# Buck_Modules.net
KiCad netlist of a schematic drawn in Altium Designer
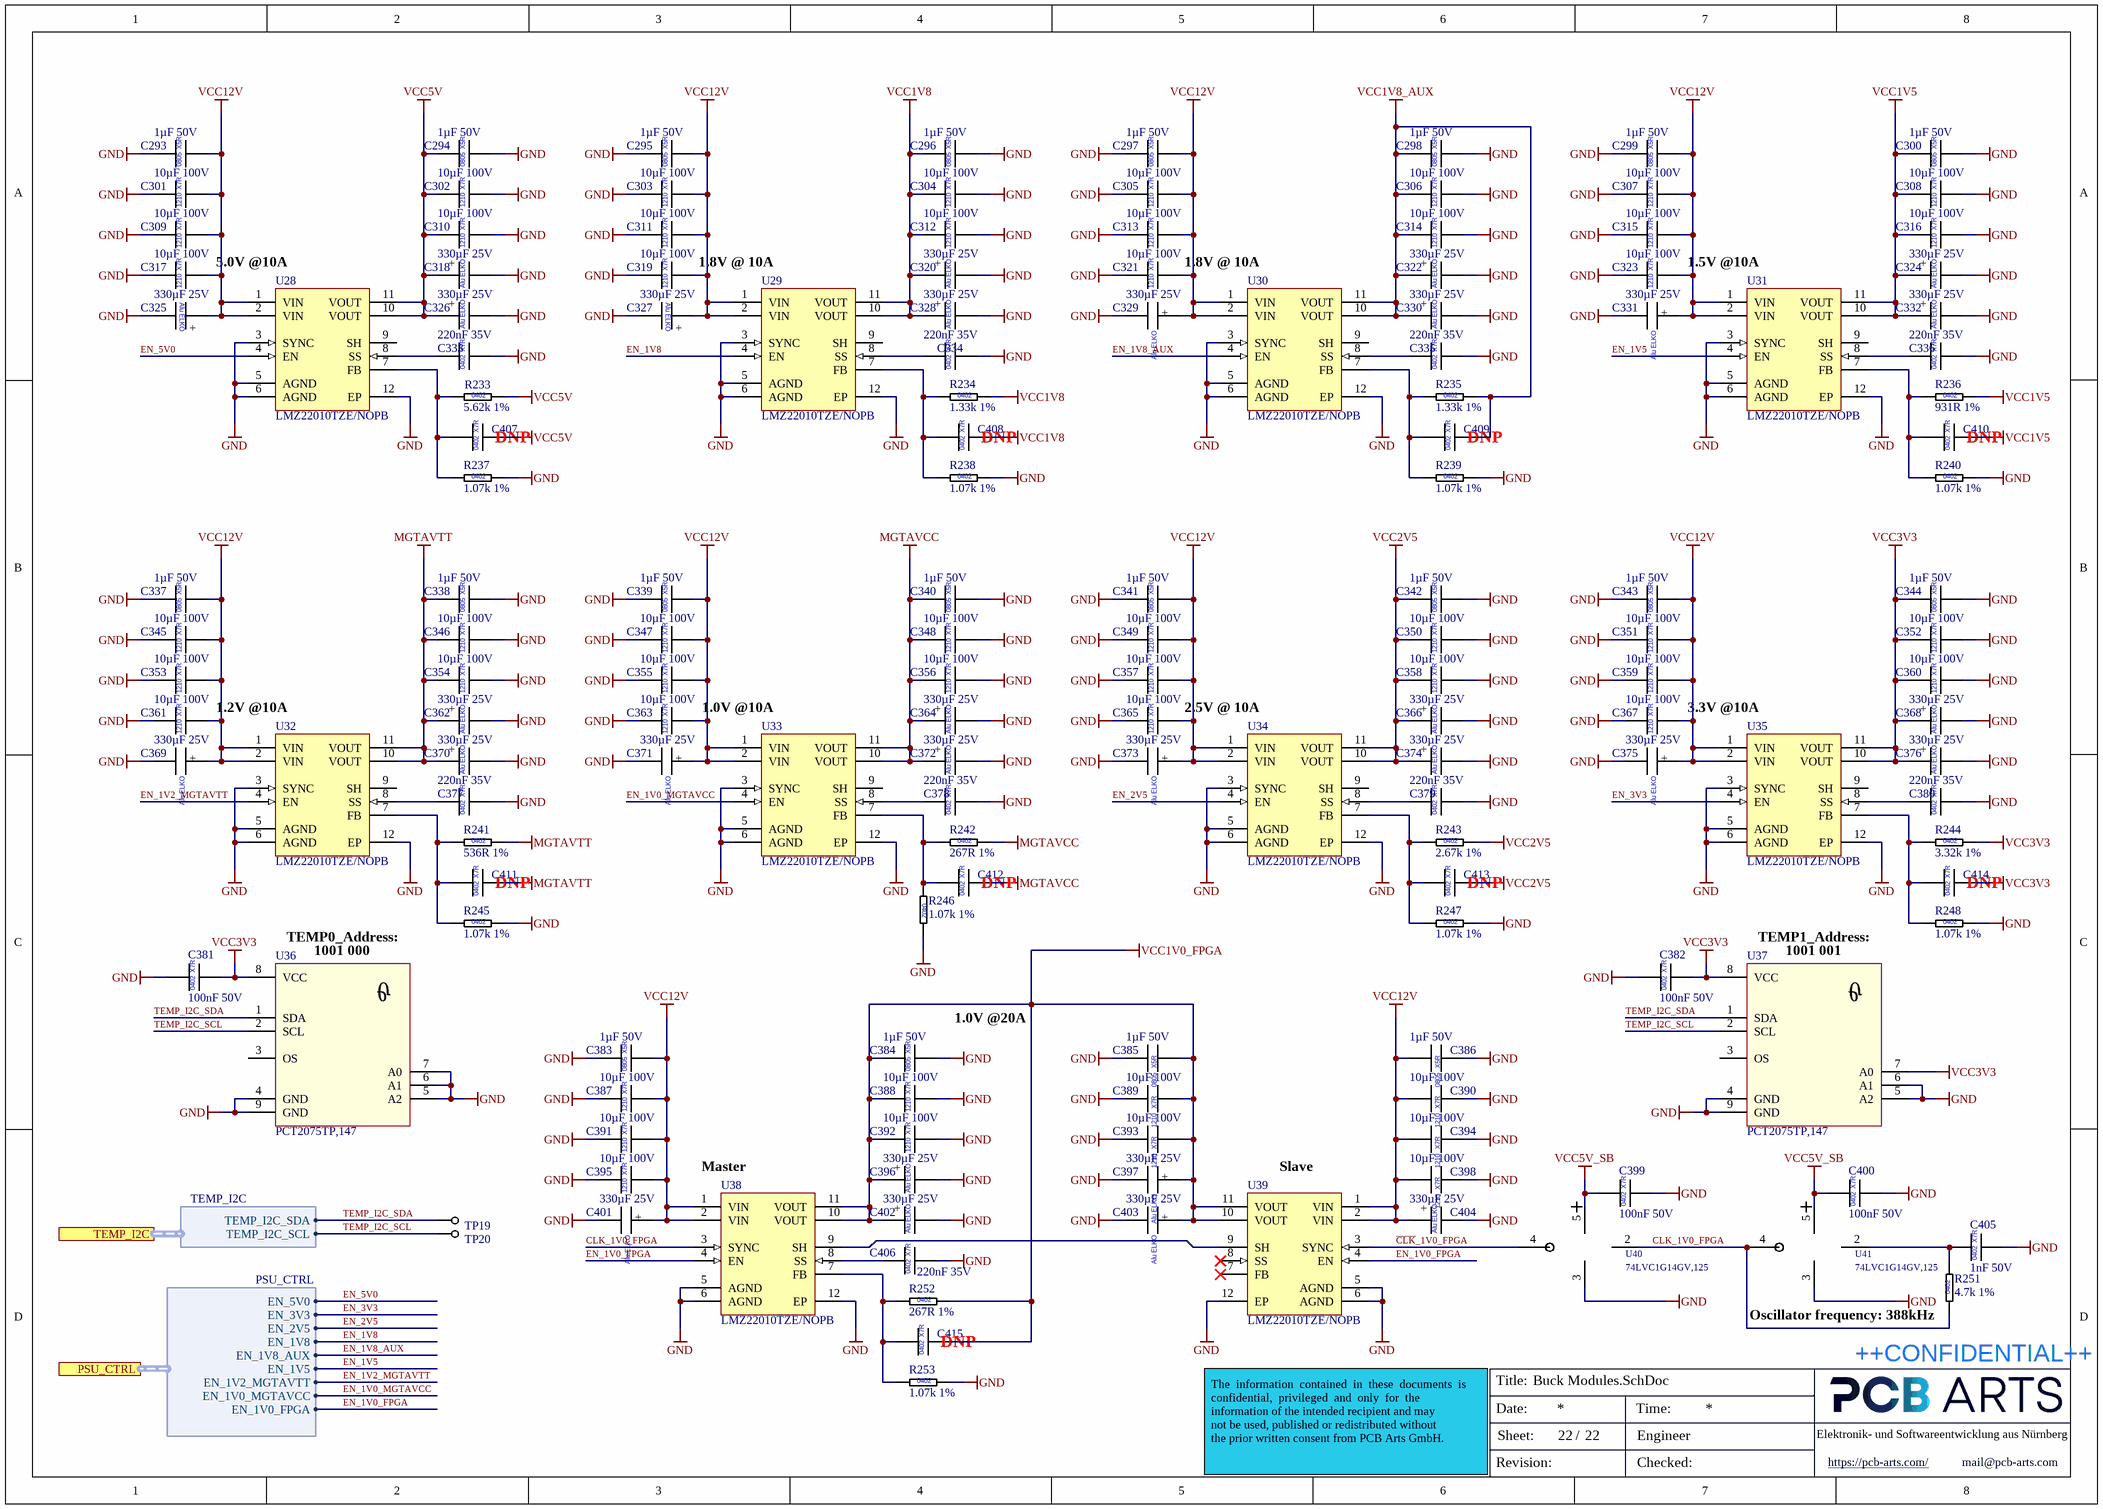
[diagram p0: Buck Modules.SchDoc]

(export (version "E")
  (design (tool "Eeschema 10.0.6"))
  (components
    (comp (ref "C293")
      (value "1µF 50V")
      (footprint "Cap:CAP_0805")
      (description "Multilayer Ceramic Capacitors MLCC - SMD/SMT 0805 50VDC")
      (libsource (lib "Cap") (part "CAP_0805_1µF_50V"))
    )
    (comp (ref "C294")
      (value "1µF 50V")
      (footprint "Cap:CAP_0805")
      (description "Multilayer Ceramic Capacitors MLCC - SMD/SMT 0805 50VDC")
      (libsource (lib "Cap") (part "CAP_0805_1µF_50V"))
    )
    (comp (ref "C295")
      (value "1µF 50V")
      (footprint "Cap:CAP_0805")
      (description "Multilayer Ceramic Capacitors MLCC - SMD/SMT 0805 50VDC")
      (libsource (lib "Cap") (part "CAP_0805_1µF_50V"))
    )
    (comp (ref "C296")
      (value "1µF 50V")
      (footprint "Cap:CAP_0805")
      (description "Multilayer Ceramic Capacitors MLCC - SMD/SMT 0805 50VDC")
      (libsource (lib "Cap") (part "CAP_0805_1µF_50V"))
    )
    (comp (ref "C297")
      (value "1µF 50V")
      (footprint "Cap:CAP_0805")
      (description "Multilayer Ceramic Capacitors MLCC - SMD/SMT 0805 50VDC")
      (libsource (lib "Cap") (part "CAP_0805_1µF_50V"))
    )
    (comp (ref "C298")
      (value "1µF 50V")
      (footprint "Cap:CAP_0805")
      (description "Multilayer Ceramic Capacitors MLCC - SMD/SMT 0805 50VDC")
      (libsource (lib "Cap") (part "CAP_0805_1µF_50V"))
    )
    (comp (ref "C299")
      (value "1µF 50V")
      (footprint "Cap:CAP_0805")
      (description "Multilayer Ceramic Capacitors MLCC - SMD/SMT 0805 50VDC")
      (libsource (lib "Cap") (part "CAP_0805_1µF_50V"))
    )
    (comp (ref "C300")
      (value "1µF 50V")
      (footprint "Cap:CAP_0805")
      (description "Multilayer Ceramic Capacitors MLCC - SMD/SMT 0805 50VDC")
      (libsource (lib "Cap") (part "CAP_0805_1µF_50V"))
    )
    (comp (ref "C301")
      (value "10µF 100V")
      (footprint "Cap:CAP_1210")
      (description "Multilayer Ceramic Capacitors MLCC - SMD/SMT 1210 100VDC")
      (libsource (lib "") (part "CAP_1210_10µF_100V_1"))
    )
    (comp (ref "C302")
      (value "10µF 100V")
      (footprint "Cap:CAP_1210")
      (description "Multilayer Ceramic Capacitors MLCC - SMD/SMT 1210 100VDC")
      (libsource (lib "") (part "CAP_1210_10µF_100V_1"))
    )
    (comp (ref "C303")
      (value "10µF 100V")
      (footprint "Cap:CAP_1210")
      (description "Multilayer Ceramic Capacitors MLCC - SMD/SMT 1210 100VDC")
      (libsource (lib "") (part "CAP_1210_10µF_100V_1"))
    )
    (comp (ref "C304")
      (value "10µF 100V")
      (footprint "Cap:CAP_1210")
      (description "Multilayer Ceramic Capacitors MLCC - SMD/SMT 1210 100VDC")
      (libsource (lib "") (part "CAP_1210_10µF_100V_1"))
    )
    (comp (ref "C305")
      (value "10µF 100V")
      (footprint "Cap:CAP_1210")
      (description "Multilayer Ceramic Capacitors MLCC - SMD/SMT 1210 100VDC")
      (libsource (lib "") (part "CAP_1210_10µF_100V_1"))
    )
    (comp (ref "C306")
      (value "10µF 100V")
      (footprint "Cap:CAP_1210")
      (description "Multilayer Ceramic Capacitors MLCC - SMD/SMT 1210 100VDC")
      (libsource (lib "") (part "CAP_1210_10µF_100V_1"))
    )
    (comp (ref "C307")
      (value "10µF 100V")
      (footprint "Cap:CAP_1210")
      (description "Multilayer Ceramic Capacitors MLCC - SMD/SMT 1210 100VDC")
      (libsource (lib "") (part "CAP_1210_10µF_100V_1"))
    )
    (comp (ref "C308")
      (value "10µF 100V")
      (footprint "Cap:CAP_1210")
      (description "Multilayer Ceramic Capacitors MLCC - SMD/SMT 1210 100VDC")
      (libsource (lib "") (part "CAP_1210_10µF_100V_1"))
    )
    (comp (ref "C309")
      (value "10µF 100V")
      (footprint "Cap:CAP_1210")
      (description "Multilayer Ceramic Capacitors MLCC - SMD/SMT 1210 100VDC")
      (libsource (lib "") (part "CAP_1210_10µF_100V_1"))
    )
    (comp (ref "C310")
      (value "10µF 100V")
      (footprint "Cap:CAP_1210")
      (description "Multilayer Ceramic Capacitors MLCC - SMD/SMT 1210 100VDC")
      (libsource (lib "") (part "CAP_1210_10µF_100V_1"))
    )
    (comp (ref "C311")
      (value "10µF 100V")
      (footprint "Cap:CAP_1210")
      (description "Multilayer Ceramic Capacitors MLCC - SMD/SMT 1210 100VDC")
      (libsource (lib "") (part "CAP_1210_10µF_100V_1"))
    )
    (comp (ref "C312")
      (value "10µF 100V")
      (footprint "Cap:CAP_1210")
      (description "Multilayer Ceramic Capacitors MLCC - SMD/SMT 1210 100VDC")
      (libsource (lib "") (part "CAP_1210_10µF_100V_1"))
    )
    (comp (ref "C313")
      (value "10µF 100V")
      (footprint "Cap:CAP_1210")
      (description "Multilayer Ceramic Capacitors MLCC - SMD/SMT 1210 100VDC")
      (libsource (lib "") (part "CAP_1210_10µF_100V_1"))
    )
    (comp (ref "C314")
      (value "10µF 100V")
      (footprint "Cap:CAP_1210")
      (description "Multilayer Ceramic Capacitors MLCC - SMD/SMT 1210 100VDC")
      (libsource (lib "") (part "CAP_1210_10µF_100V_1"))
    )
    (comp (ref "C315")
      (value "10µF 100V")
      (footprint "Cap:CAP_1210")
      (description "Multilayer Ceramic Capacitors MLCC - SMD/SMT 1210 100VDC")
      (libsource (lib "") (part "CAP_1210_10µF_100V_1"))
    )
    (comp (ref "C316")
      (value "10µF 100V")
      (footprint "Cap:CAP_1210")
      (description "Multilayer Ceramic Capacitors MLCC - SMD/SMT 1210 100VDC")
      (libsource (lib "") (part "CAP_1210_10µF_100V_1"))
    )
    (comp (ref "C317")
      (value "10µF 100V")
      (footprint "Cap:CAP_1210")
      (description "Multilayer Ceramic Capacitors MLCC - SMD/SMT 1210 100VDC")
      (libsource (lib "") (part "CAP_1210_10µF_100V_1"))
    )
    (comp (ref "C318")
      (value "330µF 25V")
      (footprint "Cap:WCAP-PTG5_D10H12.5")
      (description "Organische Polymer-Aluminiumkondensatoren 330uF 25 Volts 20% AEC-Q200")
      (libsource (lib "") (part "CAP_D10L12.5_330µF_25V_1"))
    )
    (comp (ref "C319")
      (value "10µF 100V")
      (footprint "Cap:CAP_1210")
      (description "Multilayer Ceramic Capacitors MLCC - SMD/SMT 1210 100VDC")
      (libsource (lib "") (part "CAP_1210_10µF_100V_1"))
    )
    (comp (ref "C320")
      (value "330µF 25V")
      (footprint "Cap:WCAP-PTG5_D10H12.5")
      (description "Organische Polymer-Aluminiumkondensatoren 330uF 25 Volts 20% AEC-Q200")
      (libsource (lib "") (part "CAP_D10L12.5_330µF_25V_1"))
    )
    (comp (ref "C321")
      (value "10µF 100V")
      (footprint "Cap:CAP_1210")
      (description "Multilayer Ceramic Capacitors MLCC - SMD/SMT 1210 100VDC")
      (libsource (lib "") (part "CAP_1210_10µF_100V_1"))
    )
    (comp (ref "C322")
      (value "330µF 25V")
      (footprint "Cap:WCAP-PTG5_D10H12.5")
      (description "Organische Polymer-Aluminiumkondensatoren 330uF 25 Volts 20% AEC-Q200")
      (libsource (lib "") (part "CAP_D10L12.5_330µF_25V_1"))
    )
    (comp (ref "C323")
      (value "10µF 100V")
      (footprint "Cap:CAP_1210")
      (description "Multilayer Ceramic Capacitors MLCC - SMD/SMT 1210 100VDC")
      (libsource (lib "") (part "CAP_1210_10µF_100V_1"))
    )
    (comp (ref "C324")
      (value "330µF 25V")
      (footprint "Cap:WCAP-PTG5_D10H12.5")
      (description "Organische Polymer-Aluminiumkondensatoren 330uF 25 Volts 20% AEC-Q200")
      (libsource (lib "") (part "CAP_D10L12.5_330µF_25V_1"))
    )
    (comp (ref "C325")
      (value "330µF 25V")
      (footprint "Cap:WCAP-PTG5_D10H12.5")
      (description "Organische Polymer-Aluminiumkondensatoren 330uF 25 Volts 20% AEC-Q200")
      (libsource (lib "Cap") (part "CAP_D10L12.5_330µF_25V"))
    )
    (comp (ref "C326")
      (value "330µF 25V")
      (footprint "Cap:WCAP-PTG5_D10H12.5")
      (description "Organische Polymer-Aluminiumkondensatoren 330uF 25 Volts 20% AEC-Q200")
      (libsource (lib "") (part "CAP_D10L12.5_330µF_25V_1"))
    )
    (comp (ref "C327")
      (value "330µF 25V")
      (footprint "Cap:WCAP-PTG5_D10H12.5")
      (description "Organische Polymer-Aluminiumkondensatoren 330uF 25 Volts 20% AEC-Q200")
      (libsource (lib "Cap") (part "CAP_D10L12.5_330µF_25V"))
    )
    (comp (ref "C328")
      (value "330µF 25V")
      (footprint "Cap:WCAP-PTG5_D10H12.5")
      (description "Organische Polymer-Aluminiumkondensatoren 330uF 25 Volts 20% AEC-Q200")
      (libsource (lib "") (part "CAP_D10L12.5_330µF_25V_1"))
    )
    (comp (ref "C329")
      (value "330µF 25V")
      (footprint "Cap:WCAP-PTG5_D10H12.5")
      (description "Organische Polymer-Aluminiumkondensatoren 330uF 25 Volts 20% AEC-Q200")
      (libsource (lib "Cap") (part "CAP_D10L12.5_330µF_25V"))
    )
    (comp (ref "C330")
      (value "330µF 25V")
      (footprint "Cap:WCAP-PTG5_D10H12.5")
      (description "Organische Polymer-Aluminiumkondensatoren 330uF 25 Volts 20% AEC-Q200")
      (libsource (lib "") (part "CAP_D10L12.5_330µF_25V_1"))
    )
    (comp (ref "C331")
      (value "330µF 25V")
      (footprint "Cap:WCAP-PTG5_D10H12.5")
      (description "Organische Polymer-Aluminiumkondensatoren 330uF 25 Volts 20% AEC-Q200")
      (libsource (lib "Cap") (part "CAP_D10L12.5_330µF_25V"))
    )
    (comp (ref "C332")
      (value "330µF 25V")
      (footprint "Cap:WCAP-PTG5_D10H12.5")
      (description "Organische Polymer-Aluminiumkondensatoren 330uF 25 Volts 20% AEC-Q200")
      (libsource (lib "") (part "CAP_D10L12.5_330µF_25V_1"))
    )
    (comp (ref "C333")
      (value "220nF 35V")
      (footprint "Cap:CAP_0402_L")
      (description "Multilayer Ceramic Capacitors MLCC - SMD/SMT 0402 35VDC")
      (libsource (lib "Cap") (part "CAP_0402_220nF_35V"))
    )
    (comp (ref "C334")
      (value "220nF 35V")
      (footprint "Cap:CAP_0402_L")
      (description "Multilayer Ceramic Capacitors MLCC - SMD/SMT 0402 35VDC")
      (libsource (lib "Cap") (part "CAP_0402_220nF_35V"))
    )
    (comp (ref "C335")
      (value "220nF 35V")
      (footprint "Cap:CAP_0402_L")
      (description "Multilayer Ceramic Capacitors MLCC - SMD/SMT 0402 35VDC")
      (libsource (lib "Cap") (part "CAP_0402_220nF_35V"))
    )
    (comp (ref "C336")
      (value "220nF 35V")
      (footprint "Cap:CAP_0402_L")
      (description "Multilayer Ceramic Capacitors MLCC - SMD/SMT 0402 35VDC")
      (libsource (lib "Cap") (part "CAP_0402_220nF_35V"))
    )
    (comp (ref "C337")
      (value "1µF 50V")
      (footprint "Cap:CAP_0805")
      (description "Multilayer Ceramic Capacitors MLCC - SMD/SMT 0805 50VDC")
      (libsource (lib "Cap") (part "CAP_0805_1µF_50V"))
    )
    (comp (ref "C338")
      (value "1µF 50V")
      (footprint "Cap:CAP_0805")
      (description "Multilayer Ceramic Capacitors MLCC - SMD/SMT 0805 50VDC")
      (libsource (lib "Cap") (part "CAP_0805_1µF_50V"))
    )
    (comp (ref "C339")
      (value "1µF 50V")
      (footprint "Cap:CAP_0805")
      (description "Multilayer Ceramic Capacitors MLCC - SMD/SMT 0805 50VDC")
      (libsource (lib "Cap") (part "CAP_0805_1µF_50V"))
    )
    (comp (ref "C340")
      (value "1µF 50V")
      (footprint "Cap:CAP_0805")
      (description "Multilayer Ceramic Capacitors MLCC - SMD/SMT 0805 50VDC")
      (libsource (lib "Cap") (part "CAP_0805_1µF_50V"))
    )
    (comp (ref "C341")
      (value "1µF 50V")
      (footprint "Cap:CAP_0805")
      (description "Multilayer Ceramic Capacitors MLCC - SMD/SMT 0805 50VDC")
      (libsource (lib "Cap") (part "CAP_0805_1µF_50V"))
    )
    (comp (ref "C342")
      (value "1µF 50V")
      (footprint "Cap:CAP_0805")
      (description "Multilayer Ceramic Capacitors MLCC - SMD/SMT 0805 50VDC")
      (libsource (lib "Cap") (part "CAP_0805_1µF_50V"))
    )
    (comp (ref "C343")
      (value "1µF 50V")
      (footprint "Cap:CAP_0805")
      (description "Multilayer Ceramic Capacitors MLCC - SMD/SMT 0805 50VDC")
      (libsource (lib "Cap") (part "CAP_0805_1µF_50V"))
    )
    (comp (ref "C344")
      (value "1µF 50V")
      (footprint "Cap:CAP_0805")
      (description "Multilayer Ceramic Capacitors MLCC - SMD/SMT 0805 50VDC")
      (libsource (lib "Cap") (part "CAP_0805_1µF_50V"))
    )
    (comp (ref "C345")
      (value "10µF 100V")
      (footprint "Cap:CAP_1210")
      (description "Multilayer Ceramic Capacitors MLCC - SMD/SMT 1210 100VDC")
      (libsource (lib "") (part "CAP_1210_10µF_100V_1"))
    )
    (comp (ref "C346")
      (value "10µF 100V")
      (footprint "Cap:CAP_1210")
      (description "Multilayer Ceramic Capacitors MLCC - SMD/SMT 1210 100VDC")
      (libsource (lib "") (part "CAP_1210_10µF_100V_1"))
    )
    (comp (ref "C347")
      (value "10µF 100V")
      (footprint "Cap:CAP_1210")
      (description "Multilayer Ceramic Capacitors MLCC - SMD/SMT 1210 100VDC")
      (libsource (lib "") (part "CAP_1210_10µF_100V_1"))
    )
    (comp (ref "C348")
      (value "10µF 100V")
      (footprint "Cap:CAP_1210")
      (description "Multilayer Ceramic Capacitors MLCC - SMD/SMT 1210 100VDC")
      (libsource (lib "") (part "CAP_1210_10µF_100V_1"))
    )
    (comp (ref "C349")
      (value "10µF 100V")
      (footprint "Cap:CAP_1210")
      (description "Multilayer Ceramic Capacitors MLCC - SMD/SMT 1210 100VDC")
      (libsource (lib "") (part "CAP_1210_10µF_100V_1"))
    )
    (comp (ref "C350")
      (value "10µF 100V")
      (footprint "Cap:CAP_1210")
      (description "Multilayer Ceramic Capacitors MLCC - SMD/SMT 1210 100VDC")
      (libsource (lib "") (part "CAP_1210_10µF_100V_1"))
    )
    (comp (ref "C351")
      (value "10µF 100V")
      (footprint "Cap:CAP_1210")
      (description "Multilayer Ceramic Capacitors MLCC - SMD/SMT 1210 100VDC")
      (libsource (lib "") (part "CAP_1210_10µF_100V_1"))
    )
    (comp (ref "C352")
      (value "10µF 100V")
      (footprint "Cap:CAP_1210")
      (description "Multilayer Ceramic Capacitors MLCC - SMD/SMT 1210 100VDC")
      (libsource (lib "") (part "CAP_1210_10µF_100V_1"))
    )
    (comp (ref "C353")
      (value "10µF 100V")
      (footprint "Cap:CAP_1210")
      (description "Multilayer Ceramic Capacitors MLCC - SMD/SMT 1210 100VDC")
      (libsource (lib "") (part "CAP_1210_10µF_100V_1"))
    )
    (comp (ref "C354")
      (value "10µF 100V")
      (footprint "Cap:CAP_1210")
      (description "Multilayer Ceramic Capacitors MLCC - SMD/SMT 1210 100VDC")
      (libsource (lib "") (part "CAP_1210_10µF_100V_1"))
    )
    (comp (ref "C355")
      (value "10µF 100V")
      (footprint "Cap:CAP_1210")
      (description "Multilayer Ceramic Capacitors MLCC - SMD/SMT 1210 100VDC")
      (libsource (lib "") (part "CAP_1210_10µF_100V_1"))
    )
    (comp (ref "C356")
      (value "10µF 100V")
      (footprint "Cap:CAP_1210")
      (description "Multilayer Ceramic Capacitors MLCC - SMD/SMT 1210 100VDC")
      (libsource (lib "") (part "CAP_1210_10µF_100V_1"))
    )
    (comp (ref "C357")
      (value "10µF 100V")
      (footprint "Cap:CAP_1210")
      (description "Multilayer Ceramic Capacitors MLCC - SMD/SMT 1210 100VDC")
      (libsource (lib "") (part "CAP_1210_10µF_100V_1"))
    )
    (comp (ref "C358")
      (value "10µF 100V")
      (footprint "Cap:CAP_1210")
      (description "Multilayer Ceramic Capacitors MLCC - SMD/SMT 1210 100VDC")
      (libsource (lib "") (part "CAP_1210_10µF_100V_1"))
    )
    (comp (ref "C359")
      (value "10µF 100V")
      (footprint "Cap:CAP_1210")
      (description "Multilayer Ceramic Capacitors MLCC - SMD/SMT 1210 100VDC")
      (libsource (lib "") (part "CAP_1210_10µF_100V_1"))
    )
    (comp (ref "C360")
      (value "10µF 100V")
      (footprint "Cap:CAP_1210")
      (description "Multilayer Ceramic Capacitors MLCC - SMD/SMT 1210 100VDC")
      (libsource (lib "") (part "CAP_1210_10µF_100V_1"))
    )
    (comp (ref "C361")
      (value "10µF 100V")
      (footprint "Cap:CAP_1210")
      (description "Multilayer Ceramic Capacitors MLCC - SMD/SMT 1210 100VDC")
      (libsource (lib "") (part "CAP_1210_10µF_100V_1"))
    )
    (comp (ref "C362")
      (value "330µF 25V")
      (footprint "Cap:WCAP-PTG5_D10H12.5")
      (description "Organische Polymer-Aluminiumkondensatoren 330uF 25 Volts 20% AEC-Q200")
      (libsource (lib "") (part "CAP_D10L12.5_330µF_25V_1"))
    )
    (comp (ref "C363")
      (value "10µF 100V")
      (footprint "Cap:CAP_1210")
      (description "Multilayer Ceramic Capacitors MLCC - SMD/SMT 1210 100VDC")
      (libsource (lib "") (part "CAP_1210_10µF_100V_1"))
    )
    (comp (ref "C364")
      (value "330µF 25V")
      (footprint "Cap:WCAP-PTG5_D10H12.5")
      (description "Organische Polymer-Aluminiumkondensatoren 330uF 25 Volts 20% AEC-Q200")
      (libsource (lib "") (part "CAP_D10L12.5_330µF_25V_1"))
    )
    (comp (ref "C365")
      (value "10µF 100V")
      (footprint "Cap:CAP_1210")
      (description "Multilayer Ceramic Capacitors MLCC - SMD/SMT 1210 100VDC")
      (libsource (lib "") (part "CAP_1210_10µF_100V_1"))
    )
    (comp (ref "C366")
      (value "330µF 25V")
      (footprint "Cap:WCAP-PTG5_D10H12.5")
      (description "Organische Polymer-Aluminiumkondensatoren 330uF 25 Volts 20% AEC-Q200")
      (libsource (lib "") (part "CAP_D10L12.5_330µF_25V_1"))
    )
    (comp (ref "C367")
      (value "10µF 100V")
      (footprint "Cap:CAP_1210")
      (description "Multilayer Ceramic Capacitors MLCC - SMD/SMT 1210 100VDC")
      (libsource (lib "") (part "CAP_1210_10µF_100V_1"))
    )
    (comp (ref "C368")
      (value "330µF 25V")
      (footprint "Cap:WCAP-PTG5_D10H12.5")
      (description "Organische Polymer-Aluminiumkondensatoren 330uF 25 Volts 20% AEC-Q200")
      (libsource (lib "") (part "CAP_D10L12.5_330µF_25V_1"))
    )
    (comp (ref "C369")
      (value "330µF 25V")
      (footprint "Cap:WCAP-PTG5_D10H12.5")
      (description "Organische Polymer-Aluminiumkondensatoren 330uF 25 Volts 20% AEC-Q200")
      (libsource (lib "Cap") (part "CAP_D10L12.5_330µF_25V"))
    )
    (comp (ref "C370")
      (value "330µF 25V")
      (footprint "Cap:WCAP-PTG5_D10H12.5")
      (description "Organische Polymer-Aluminiumkondensatoren 330uF 25 Volts 20% AEC-Q200")
      (libsource (lib "") (part "CAP_D10L12.5_330µF_25V_1"))
    )
    (comp (ref "C371")
      (value "330µF 25V")
      (footprint "Cap:WCAP-PTG5_D10H12.5")
      (description "Organische Polymer-Aluminiumkondensatoren 330uF 25 Volts 20% AEC-Q200")
      (libsource (lib "Cap") (part "CAP_D10L12.5_330µF_25V"))
    )
    (comp (ref "C372")
      (value "330µF 25V")
      (footprint "Cap:WCAP-PTG5_D10H12.5")
      (description "Organische Polymer-Aluminiumkondensatoren 330uF 25 Volts 20% AEC-Q200")
      (libsource (lib "") (part "CAP_D10L12.5_330µF_25V_1"))
    )
    (comp (ref "C373")
      (value "330µF 25V")
      (footprint "Cap:WCAP-PTG5_D10H12.5")
      (description "Organische Polymer-Aluminiumkondensatoren 330uF 25 Volts 20% AEC-Q200")
      (libsource (lib "Cap") (part "CAP_D10L12.5_330µF_25V"))
    )
    (comp (ref "C374")
      (value "330µF 25V")
      (footprint "Cap:WCAP-PTG5_D10H12.5")
      (description "Organische Polymer-Aluminiumkondensatoren 330uF 25 Volts 20% AEC-Q200")
      (libsource (lib "") (part "CAP_D10L12.5_330µF_25V_1"))
    )
    (comp (ref "C375")
      (value "330µF 25V")
      (footprint "Cap:WCAP-PTG5_D10H12.5")
      (description "Organische Polymer-Aluminiumkondensatoren 330uF 25 Volts 20% AEC-Q200")
      (libsource (lib "Cap") (part "CAP_D10L12.5_330µF_25V"))
    )
    (comp (ref "C376")
      (value "330µF 25V")
      (footprint "Cap:WCAP-PTG5_D10H12.5")
      (description "Organische Polymer-Aluminiumkondensatoren 330uF 25 Volts 20% AEC-Q200")
      (libsource (lib "") (part "CAP_D10L12.5_330µF_25V_1"))
    )
    (comp (ref "C377")
      (value "220nF 35V")
      (footprint "Cap:CAP_0402_L")
      (description "Multilayer Ceramic Capacitors MLCC - SMD/SMT 0402 35VDC")
      (libsource (lib "Cap") (part "CAP_0402_220nF_35V"))
    )
    (comp (ref "C378")
      (value "220nF 35V")
      (footprint "Cap:CAP_0402_L")
      (description "Multilayer Ceramic Capacitors MLCC - SMD/SMT 0402 35VDC")
      (libsource (lib "Cap") (part "CAP_0402_220nF_35V"))
    )
    (comp (ref "C379")
      (value "220nF 35V")
      (footprint "Cap:CAP_0402_L")
      (description "Multilayer Ceramic Capacitors MLCC - SMD/SMT 0402 35VDC")
      (libsource (lib "Cap") (part "CAP_0402_220nF_35V"))
    )
    (comp (ref "C380")
      (value "220nF 35V")
      (footprint "Cap:CAP_0402_L")
      (description "Multilayer Ceramic Capacitors MLCC - SMD/SMT 0402 35VDC")
      (libsource (lib "Cap") (part "CAP_0402_220nF_35V"))
    )
    (comp (ref "C381")
      (value "100nF 50V")
      (footprint "Cap:CAP_0402_L")
      (description "Multilayer Ceramic Capacitors MLCC - SMD/SMT 0402 50VDC")
      (libsource (lib "Cap") (part "CAP_0402_100nF_50V"))
    )
    (comp (ref "C382")
      (value "100nF 50V")
      (footprint "Cap:CAP_0402_L")
      (description "Multilayer Ceramic Capacitors MLCC - SMD/SMT 0402 50VDC")
      (libsource (lib "Cap") (part "CAP_0402_100nF_50V"))
    )
    (comp (ref "C383")
      (value "1µF 50V")
      (footprint "Cap:CAP_0805")
      (description "Multilayer Ceramic Capacitors MLCC - SMD/SMT 0805 50VDC")
      (libsource (lib "Cap") (part "CAP_0805_1µF_50V"))
    )
    (comp (ref "C384")
      (value "1µF 50V")
      (footprint "Cap:CAP_0805")
      (description "Multilayer Ceramic Capacitors MLCC - SMD/SMT 0805 50VDC")
      (libsource (lib "Cap") (part "CAP_0805_1µF_50V"))
    )
    (comp (ref "C385")
      (value "1µF 50V")
      (footprint "Cap:CAP_0805")
      (description "Multilayer Ceramic Capacitors MLCC - SMD/SMT 0805 50VDC")
      (libsource (lib "") (part "CAP_0805_1µF_50V_1"))
    )
    (comp (ref "C386")
      (value "1µF 50V")
      (footprint "Cap:CAP_0805")
      (description "Multilayer Ceramic Capacitors MLCC - SMD/SMT 0805 50VDC")
      (libsource (lib "") (part "CAP_0805_1µF_50V_1"))
    )
    (comp (ref "C387")
      (value "10µF 100V")
      (footprint "Cap:CAP_1210")
      (description "Multilayer Ceramic Capacitors MLCC - SMD/SMT 1210 100VDC")
      (libsource (lib "") (part "CAP_1210_10µF_100V_1"))
    )
    (comp (ref "C388")
      (value "10µF 100V")
      (footprint "Cap:CAP_1210")
      (description "Multilayer Ceramic Capacitors MLCC - SMD/SMT 1210 100VDC")
      (libsource (lib "") (part "CAP_1210_10µF_100V_1"))
    )
    (comp (ref "C389")
      (value "10µF 100V")
      (footprint "Cap:CAP_1210")
      (description "Multilayer Ceramic Capacitors MLCC - SMD/SMT 1210 100VDC")
      (libsource (lib "Cap") (part "CAP_1210_10µF_100V"))
    )
    (comp (ref "C390")
      (value "10µF 100V")
      (footprint "Cap:CAP_1210")
      (description "Multilayer Ceramic Capacitors MLCC - SMD/SMT 1210 100VDC")
      (libsource (lib "Cap") (part "CAP_1210_10µF_100V"))
    )
    (comp (ref "C391")
      (value "10µF 100V")
      (footprint "Cap:CAP_1210")
      (description "Multilayer Ceramic Capacitors MLCC - SMD/SMT 1210 100VDC")
      (libsource (lib "") (part "CAP_1210_10µF_100V_1"))
    )
    (comp (ref "C392")
      (value "10µF 100V")
      (footprint "Cap:CAP_1210")
      (description "Multilayer Ceramic Capacitors MLCC - SMD/SMT 1210 100VDC")
      (libsource (lib "") (part "CAP_1210_10µF_100V_1"))
    )
    (comp (ref "C393")
      (value "10µF 100V")
      (footprint "Cap:CAP_1210")
      (description "Multilayer Ceramic Capacitors MLCC - SMD/SMT 1210 100VDC")
      (libsource (lib "Cap") (part "CAP_1210_10µF_100V"))
    )
    (comp (ref "C394")
      (value "10µF 100V")
      (footprint "Cap:CAP_1210")
      (description "Multilayer Ceramic Capacitors MLCC - SMD/SMT 1210 100VDC")
      (libsource (lib "Cap") (part "CAP_1210_10µF_100V"))
    )
    (comp (ref "C395")
      (value "10µF 100V")
      (footprint "Cap:CAP_1210")
      (description "Multilayer Ceramic Capacitors MLCC - SMD/SMT 1210 100VDC")
      (libsource (lib "") (part "CAP_1210_10µF_100V_1"))
    )
    (comp (ref "C396")
      (value "330µF 25V")
      (footprint "Cap:WCAP-PTG5_D10H12.5")
      (description "Organische Polymer-Aluminiumkondensatoren 330uF 25 Volts 20% AEC-Q200")
      (libsource (lib "") (part "CAP_D10L12.5_330µF_25V_1"))
    )
    (comp (ref "C397")
      (value "330µF 25V")
      (footprint "Cap:WCAP-PTG5_D10H12.5")
      (description "Organische Polymer-Aluminiumkondensatoren 330uF 25 Volts 20% AEC-Q200")
      (libsource (lib "Cap") (part "CAP_D10L12.5_330µF_25V"))
    )
    (comp (ref "C398")
      (value "10µF 100V")
      (footprint "Cap:CAP_1210")
      (description "Multilayer Ceramic Capacitors MLCC - SMD/SMT 1210 100VDC")
      (libsource (lib "Cap") (part "CAP_1210_10µF_100V"))
    )
    (comp (ref "C399")
      (value "100nF 50V")
      (footprint "Cap:CAP_0402_L")
      (description "Multilayer Ceramic Capacitors MLCC - SMD/SMT 0402 50VDC")
      (libsource (lib "Cap") (part "CAP_0402_100nF_50V"))
    )
    (comp (ref "C400")
      (value "100nF 50V")
      (footprint "Cap:CAP_0402_L")
      (description "Multilayer Ceramic Capacitors MLCC - SMD/SMT 0402 50VDC")
      (libsource (lib "Cap") (part "CAP_0402_100nF_50V"))
    )
    (comp (ref "C401")
      (value "330µF 25V")
      (footprint "Cap:WCAP-PTG5_D10H12.5")
      (description "Organische Polymer-Aluminiumkondensatoren 330uF 25 Volts 20% AEC-Q200")
      (libsource (lib "Cap") (part "CAP_D10L12.5_330µF_25V"))
    )
    (comp (ref "C402")
      (value "330µF 25V")
      (footprint "Cap:WCAP-PTG5_D10H12.5")
      (description "Organische Polymer-Aluminiumkondensatoren 330uF 25 Volts 20% AEC-Q200")
      (libsource (lib "") (part "CAP_D10L12.5_330µF_25V_1"))
    )
    (comp (ref "C403")
      (value "330µF 25V")
      (footprint "Cap:WCAP-PTG5_D10H12.5")
      (description "Organische Polymer-Aluminiumkondensatoren 330uF 25 Volts 20% AEC-Q200")
      (libsource (lib "Cap") (part "CAP_D10L12.5_330µF_25V"))
    )
    (comp (ref "C404")
      (value "330µF 25V")
      (footprint "Cap:WCAP-PTG5_D10H12.5")
      (description "Organische Polymer-Aluminiumkondensatoren 330uF 25 Volts 20% AEC-Q200")
      (libsource (lib "") (part "CAP_D10L12.5_330µF_25V_1"))
    )
    (comp (ref "C405")
      (value "1nF 50V")
      (footprint "Cap:CAP_0402_L")
      (description "Multilayer Ceramic Capacitors MLCC - SMD/SMT 0402 50VDC")
      (libsource (lib "Cap") (part "CAP_0402_1nF_50V"))
    )
    (comp (ref "C406")
      (value "220nF 35V")
      (footprint "Cap:CAP_0402_L")
      (description "Multilayer Ceramic Capacitors MLCC - SMD/SMT 0402 35VDC")
      (libsource (lib "Cap") (part "CAP_0402_220nF_35V"))
    )
    (comp (ref "C407")
      (value "OPT")
      (footprint "Cap:CAP_0402_L")
      (description "Multilayer Ceramic Capacitors MLCC - SMD/SMT 0402 Optional Placeholder")
      (libsource (lib "Cap") (part "CAP_0402_OPT"))
    )
    (comp (ref "C408")
      (value "OPT")
      (footprint "Cap:CAP_0402_L")
      (description "Multilayer Ceramic Capacitors MLCC - SMD/SMT 0402 Optional Placeholder")
      (libsource (lib "Cap") (part "CAP_0402_OPT"))
    )
    (comp (ref "C409")
      (value "OPT")
      (footprint "Cap:CAP_0402_L")
      (description "Multilayer Ceramic Capacitors MLCC - SMD/SMT 0402 Optional Placeholder")
      (libsource (lib "Cap") (part "CAP_0402_OPT"))
    )
    (comp (ref "C410")
      (value "OPT")
      (footprint "Cap:CAP_0402_L")
      (description "Multilayer Ceramic Capacitors MLCC - SMD/SMT 0402 Optional Placeholder")
      (libsource (lib "Cap") (part "CAP_0402_OPT"))
    )
    (comp (ref "C411")
      (value "OPT")
      (footprint "Cap:CAP_0402_L")
      (description "Multilayer Ceramic Capacitors MLCC - SMD/SMT 0402 Optional Placeholder")
      (libsource (lib "Cap") (part "CAP_0402_OPT"))
    )
    (comp (ref "C412")
      (value "OPT")
      (footprint "Cap:CAP_0402_L")
      (description "Multilayer Ceramic Capacitors MLCC - SMD/SMT 0402 Optional Placeholder")
      (libsource (lib "Cap") (part "CAP_0402_OPT"))
    )
    (comp (ref "C413")
      (value "OPT")
      (footprint "Cap:CAP_0402_L")
      (description "Multilayer Ceramic Capacitors MLCC - SMD/SMT 0402 Optional Placeholder")
      (libsource (lib "Cap") (part "CAP_0402_OPT"))
    )
    (comp (ref "C414")
      (value "OPT")
      (footprint "Cap:CAP_0402_L")
      (description "Multilayer Ceramic Capacitors MLCC - SMD/SMT 0402 Optional Placeholder")
      (libsource (lib "Cap") (part "CAP_0402_OPT"))
    )
    (comp (ref "C415")
      (value "OPT")
      (footprint "Cap:CAP_0402_L")
      (description "Multilayer Ceramic Capacitors MLCC - SMD/SMT 0402 Optional Placeholder")
      (libsource (lib "Cap") (part "CAP_0402_OPT"))
    )
    (comp (ref "R233")
      (value "5.62k 1%")
      (footprint "Res:RES_0402_L")
      (description "Thick Film Resistors - SMD 5.62kOhm 1%")
      (libsource (lib "Res") (part "RES_0402_5.62k_1%"))
    )
    (comp (ref "R234")
      (value "1.33k 1%")
      (footprint "Res:RES_0402_L")
      (description "Thick Film Resistors - SMD 1.33kOhm 1%")
      (libsource (lib "Res") (part "RES_0402_1.33k_1%"))
    )
    (comp (ref "R235")
      (value "1.33k 1%")
      (footprint "Res:RES_0402_L")
      (description "Thick Film Resistors - SMD 1.33kOhm 1%")
      (libsource (lib "Res") (part "RES_0402_1.33k_1%"))
    )
    (comp (ref "R236")
      (value "931R 1%")
      (footprint "Res:RES_0402_L")
      (description "Thick Film Resistors - SMD 931Ohm 1%")
      (libsource (lib "Res") (part "RES_0402_931R_1%"))
    )
    (comp (ref "R237")
      (value "1.07k 1%")
      (footprint "Res:RES_0402_L")
      (description "Thick Film Resistors - SMD 1.07kOhm 1%")
      (libsource (lib "Res") (part "RES_0402_1.07k_1%"))
    )
    (comp (ref "R238")
      (value "1.07k 1%")
      (footprint "Res:RES_0402_L")
      (description "Thick Film Resistors - SMD 1.07kOhm 1%")
      (libsource (lib "Res") (part "RES_0402_1.07k_1%"))
    )
    (comp (ref "R239")
      (value "1.07k 1%")
      (footprint "Res:RES_0402_L")
      (description "Thick Film Resistors - SMD 1.07kOhm 1%")
      (libsource (lib "Res") (part "RES_0402_1.07k_1%"))
    )
    (comp (ref "R240")
      (value "1.07k 1%")
      (footprint "Res:RES_0402_L")
      (description "Thick Film Resistors - SMD 1.07kOhm 1%")
      (libsource (lib "Res") (part "RES_0402_1.07k_1%"))
    )
    (comp (ref "R241")
      (value "536R 1%")
      (footprint "Res:RES_0402_L")
      (description "Thick Film Resistors - SMD 536Ohm 1%")
      (libsource (lib "Res") (part "RES_0402_536R_1%"))
    )
    (comp (ref "R242")
      (value "267R 1%")
      (footprint "Res:RES_0402_L")
      (description "Thick Film Resistors - SMD 267Ohm 1%")
      (libsource (lib "Res") (part "RES_0402_267R_1%"))
    )
    (comp (ref "R243")
      (value "2.67k 1%")
      (footprint "Res:RES_0402_L")
      (description "Thick Film Resistors - SMD 2.67kOhm 1%")
      (libsource (lib "Res") (part "RES_0402_2.67k_1%"))
    )
    (comp (ref "R244")
      (value "3.32k 1%")
      (footprint "Res:RES_0402_L")
      (description "Thick Film Resistors - SMD 3.32kOhm 1%")
      (libsource (lib "Res") (part "RES_0402_3.32k_1%"))
    )
    (comp (ref "R245")
      (value "1.07k 1%")
      (footprint "Res:RES_0402_L")
      (description "Thick Film Resistors - SMD 1.07kOhm 1%")
      (libsource (lib "Res") (part "RES_0402_1.07k_1%"))
    )
    (comp (ref "R246")
      (value "1.07k 1%")
      (footprint "Res:RES_0402_L")
      (description "Thick Film Resistors - SMD 1.07kOhm 1%")
      (libsource (lib "Res") (part "RES_0402_1.07k_1%"))
    )
    (comp (ref "R247")
      (value "1.07k 1%")
      (footprint "Res:RES_0402_L")
      (description "Thick Film Resistors - SMD 1.07kOhm 1%")
      (libsource (lib "Res") (part "RES_0402_1.07k_1%"))
    )
    (comp (ref "R248")
      (value "1.07k 1%")
      (footprint "Res:RES_0402_L")
      (description "Thick Film Resistors - SMD 1.07kOhm 1%")
      (libsource (lib "Res") (part "RES_0402_1.07k_1%"))
    )
    (comp (ref "R251")
      (value "4.7k 1%")
      (footprint "Res:RES_0402_L")
      (description "Thick Film Resistors - SMD 4.7kOhm 1%")
      (libsource (lib "Res") (part "RES_0402_4.7k_1%"))
    )
    (comp (ref "R252")
      (value "267R 1%")
      (footprint "Res:RES_0402_L")
      (description "Thick Film Resistors - SMD 267Ohm 1%")
      (libsource (lib "Res") (part "RES_0402_267R_1%"))
    )
    (comp (ref "R253")
      (value "1.07k 1%")
      (footprint "Res:RES_0402_L")
      (description "Thick Film Resistors - SMD 1.07kOhm 1%")
      (libsource (lib "Res") (part "RES_0402_1.07k_1%"))
    )
    (comp (ref "TP19")
      (value "Testpoint")
      (footprint "Electro_mech:Testpoint 0.8mm")
      (description "Testpoint 0.8mm")
      (libsource (lib "Electro_Mech") (part "Testpoint 0.8mm"))
    )
    (comp (ref "TP20")
      (value "Testpoint")
      (footprint "Electro_mech:Testpoint 0.8mm")
      (description "Testpoint 0.8mm")
      (libsource (lib "Electro_Mech") (part "Testpoint 0.8mm"))
    )
    (comp (ref "U28")
      (value "LMZ22010TZE/NOPB")
      (footprint "power:TI Simpleswitcher NDY0011A_N")
      (description "10A SIMPLE SWITCHER® Power Module with 20V Maximum Input and Current Sharing")
      (libsource (lib "Power") (part "LMZ22010TZE/NOPB_Power Module with 20V Maximum Input and Current Sharing"))
    )
    (comp (ref "U29")
      (value "LMZ22010TZE/NOPB")
      (footprint "power:TI Simpleswitcher NDY0011A_N")
      (description "10A SIMPLE SWITCHER® Power Module with 20V Maximum Input and Current Sharing")
      (libsource (lib "Power") (part "LMZ22010TZE/NOPB_Power Module with 20V Maximum Input and Current Sharing"))
    )
    (comp (ref "U30")
      (value "LMZ22010TZE/NOPB")
      (footprint "power:TI Simpleswitcher NDY0011A_N")
      (description "10A SIMPLE SWITCHER® Power Module with 20V Maximum Input and Current Sharing")
      (libsource (lib "Power") (part "LMZ22010TZE/NOPB_Power Module with 20V Maximum Input and Current Sharing"))
    )
    (comp (ref "U31")
      (value "LMZ22010TZE/NOPB")
      (footprint "power:TI Simpleswitcher NDY0011A_N")
      (description "10A SIMPLE SWITCHER® Power Module with 20V Maximum Input and Current Sharing")
      (libsource (lib "Power") (part "LMZ22010TZE/NOPB_Power Module with 20V Maximum Input and Current Sharing"))
    )
    (comp (ref "U32")
      (value "LMZ22010TZE/NOPB")
      (footprint "power:TI Simpleswitcher NDY0011A_N")
      (description "10A SIMPLE SWITCHER® Power Module with 20V Maximum Input and Current Sharing")
      (libsource (lib "Power") (part "LMZ22010TZE/NOPB_Power Module with 20V Maximum Input and Current Sharing"))
    )
    (comp (ref "U33")
      (value "LMZ22010TZE/NOPB")
      (footprint "power:TI Simpleswitcher NDY0011A_N")
      (description "10A SIMPLE SWITCHER® Power Module with 20V Maximum Input and Current Sharing")
      (libsource (lib "Power") (part "LMZ22010TZE/NOPB_Power Module with 20V Maximum Input and Current Sharing"))
    )
    (comp (ref "U34")
      (value "LMZ22010TZE/NOPB")
      (footprint "power:TI Simpleswitcher NDY0011A_N")
      (description "10A SIMPLE SWITCHER® Power Module with 20V Maximum Input and Current Sharing")
      (libsource (lib "Power") (part "LMZ22010TZE/NOPB_Power Module with 20V Maximum Input and Current Sharing"))
    )
    (comp (ref "U35")
      (value "LMZ22010TZE/NOPB")
      (footprint "power:TI Simpleswitcher NDY0011A_N")
      (description "10A SIMPLE SWITCHER® Power Module with 20V Maximum Input and Current Sharing")
      (libsource (lib "Power") (part "LMZ22010TZE/NOPB_Power Module with 20V Maximum Input and Current Sharing"))
    )
    (comp (ref "U36")
      (value "PCT2075TP,147")
      (footprint "Active:SOT1069-2 (HWSON8)")
      (description "Digital Temp Sensor I2C")
      (libsource (lib "Active") (part "PCT2075TP,147"))
    )
    (comp (ref "U37")
      (value "PCT2075TP,147")
      (footprint "Active:SOT1069-2 (HWSON8)")
      (description "Digital Temp Sensor I2C")
      (libsource (lib "Active") (part "PCT2075TP,147"))
    )
    (comp (ref "U38")
      (value "LMZ22010TZE/NOPB")
      (footprint "power:TI Simpleswitcher NDY0011A_N")
      (description "10A SIMPLE SWITCHER® Power Module with 20V Maximum Input and Current Sharing")
      (libsource (lib "Power") (part "LMZ22010TZE/NOPB_Power Module with 20V Maximum Input and Current Sharing"))
    )
    (comp (ref "U39")
      (value "LMZ22010TZE/NOPB")
      (footprint "power:TI Simpleswitcher NDY0011A_N")
      (description "10A SIMPLE SWITCHER® Power Module with 20V Maximum Input and Current Sharing")
      (libsource (lib "") (part "LMZ22010TZE/NOPB_Power Module with 20V Maximum Input and Current Sharing_1"))
    )
    (comp (ref "U40")
      (value "74LVC1G14GV,125")
      (footprint "Digital:SOT95P275X110-5N")
      (description "Inverter Single inverting Schmitt trigger")
      (libsource (lib "Digital") (part "74LVC1G14GV,125_Inverter Single inverting Schmitt trigger"))
    )
    (comp (ref "U41")
      (value "74LVC1G14GV,125")
      (footprint "Digital:SOT95P275X110-5N")
      (description "Inverter Single inverting Schmitt trigger")
      (libsource (lib "Digital") (part "74LVC1G14GV,125_Inverter Single inverting Schmitt trigger"))
    )
  )
  (nets
    (net (code "3") (name "/CLK_1V0_FPGA") (class "Default")
      (node (ref "R251") (pin "1") (pinfunction "1_1") (pintype "passive"))
      (node (ref "U38") (pin "3") (pinfunction "SYNC_3") (pintype "input"))
      (node (ref "U40") (pin "2") (pinfunction "A_2") (pintype "passive"))
      (node (ref "U41") (pin "4") (pinfunction "Y_4") (pintype "passive"))
    )
    (net (code "4") (name "/EN_1V0_FPGA") (class "Default")
      (node (ref "U38") (pin "4") (pinfunction "EN_4") (pintype "input"))
      (node (ref "U39") (pin "4") (pinfunction "EN_4") (pintype "input"))
    )
    (net (code "5") (name "/EN_1V0_MGTAVCC") (class "Default")
      (node (ref "U33") (pin "4") (pinfunction "EN_4") (pintype "input"))
    )
    (net (code "6") (name "/EN_1V2_MGTAVTT") (class "Default")
      (node (ref "U32") (pin "4") (pinfunction "EN_4") (pintype "input"))
    )
    (net (code "7") (name "/EN_1V5") (class "Default")
      (node (ref "U31") (pin "4") (pinfunction "EN_4") (pintype "input"))
    )
    (net (code "8") (name "/EN_1V8") (class "Default")
      (node (ref "U29") (pin "4") (pinfunction "EN_4") (pintype "input"))
    )
    (net (code "9") (name "/EN_1V8_AUX") (class "Default")
      (node (ref "U30") (pin "4") (pinfunction "EN_4") (pintype "input"))
    )
    (net (code "10") (name "/EN_2V5") (class "Default")
      (node (ref "U34") (pin "4") (pinfunction "EN_4") (pintype "input"))
    )
    (net (code "11") (name "/EN_3V3") (class "Default")
      (node (ref "U35") (pin "4") (pinfunction "EN_4") (pintype "input"))
    )
    (net (code "12") (name "/EN_5V0") (class "Default")
      (node (ref "U28") (pin "4") (pinfunction "EN_4") (pintype "input"))
    )
    (net (code "13") (name "/TEMP_I2C_SCL") (class "Default")
      (node (ref "TP20") (pin "1") (pinfunction "GND_1") (pintype "passive"))
      (node (ref "U36") (pin "2") (pinfunction "SCL_2") (pintype "passive"))
      (node (ref "U37") (pin "2") (pinfunction "SCL_2") (pintype "passive"))
    )
    (net (code "14") (name "/TEMP_I2C_SDA") (class "Default")
      (node (ref "TP19") (pin "1") (pinfunction "GND_1") (pintype "passive"))
      (node (ref "U36") (pin "1") (pinfunction "SDA_1") (pintype "passive"))
      (node (ref "U37") (pin "1") (pinfunction "SDA_1") (pintype "passive"))
    )
    (net (code "17") (name "/~{CLK}_1V0_FPGA") (class "Default")
      (node (ref "U39") (pin "3") (pinfunction "SYNC_3") (pintype "input"))
      (node (ref "U40") (pin "4") (pinfunction "Y_4") (pintype "passive"))
    )
    (net (code "18") (name "GND") (class "Default")
      (node (ref "C293") (pin "1") (pinfunction "1_1") (pintype "passive"))
      (node (ref "C294") (pin "2") (pinfunction "2_2") (pintype "passive"))
      (node (ref "C295") (pin "1") (pinfunction "1_1") (pintype "passive"))
      (node (ref "C296") (pin "2") (pinfunction "2_2") (pintype "passive"))
      (node (ref "C297") (pin "1") (pinfunction "1_1") (pintype "passive"))
      (node (ref "C298") (pin "2") (pinfunction "2_2") (pintype "passive"))
      (node (ref "C299") (pin "1") (pinfunction "1_1") (pintype "passive"))
      (node (ref "C300") (pin "2") (pinfunction "2_2") (pintype "passive"))
      (node (ref "C301") (pin "1") (pinfunction "1_1") (pintype "passive"))
      (node (ref "C302") (pin "2") (pinfunction "2_2") (pintype "passive"))
      (node (ref "C303") (pin "1") (pinfunction "1_1") (pintype "passive"))
      (node (ref "C304") (pin "2") (pinfunction "2_2") (pintype "passive"))
      (node (ref "C305") (pin "1") (pinfunction "1_1") (pintype "passive"))
      (node (ref "C306") (pin "2") (pinfunction "2_2") (pintype "passive"))
      (node (ref "C307") (pin "1") (pinfunction "1_1") (pintype "passive"))
      (node (ref "C308") (pin "2") (pinfunction "2_2") (pintype "passive"))
      (node (ref "C309") (pin "1") (pinfunction "1_1") (pintype "passive"))
      (node (ref "C310") (pin "2") (pinfunction "2_2") (pintype "passive"))
      (node (ref "C311") (pin "1") (pinfunction "1_1") (pintype "passive"))
      (node (ref "C312") (pin "2") (pinfunction "2_2") (pintype "passive"))
      (node (ref "C313") (pin "1") (pinfunction "1_1") (pintype "passive"))
      (node (ref "C314") (pin "2") (pinfunction "2_2") (pintype "passive"))
      (node (ref "C315") (pin "1") (pinfunction "1_1") (pintype "passive"))
      (node (ref "C316") (pin "2") (pinfunction "2_2") (pintype "passive"))
      (node (ref "C317") (pin "1") (pinfunction "1_1") (pintype "passive"))
      (node (ref "C318") (pin "2") (pinfunction "2_2") (pintype "passive"))
      (node (ref "C319") (pin "1") (pinfunction "1_1") (pintype "passive"))
      (node (ref "C320") (pin "2") (pinfunction "2_2") (pintype "passive"))
      (node (ref "C321") (pin "1") (pinfunction "1_1") (pintype "passive"))
      (node (ref "C322") (pin "2") (pinfunction "2_2") (pintype "passive"))
      (node (ref "C323") (pin "1") (pinfunction "1_1") (pintype "passive"))
      (node (ref "C324") (pin "2") (pinfunction "2_2") (pintype "passive"))
      (node (ref "C325") (pin "2") (pinfunction "2_2") (pintype "passive"))
      (node (ref "C326") (pin "2") (pinfunction "2_2") (pintype "passive"))
      (node (ref "C327") (pin "2") (pinfunction "2_2") (pintype "passive"))
      (node (ref "C328") (pin "2") (pinfunction "2_2") (pintype "passive"))
      (node (ref "C329") (pin "2") (pinfunction "2_2") (pintype "passive"))
      (node (ref "C330") (pin "2") (pinfunction "2_2") (pintype "passive"))
      (node (ref "C331") (pin "2") (pinfunction "2_2") (pintype "passive"))
      (node (ref "C332") (pin "2") (pinfunction "2_2") (pintype "passive"))
      (node (ref "C333") (pin "2") (pinfunction "2_2") (pintype "passive"))
      (node (ref "C334") (pin "2") (pinfunction "2_2") (pintype "passive"))
      (node (ref "C335") (pin "2") (pinfunction "2_2") (pintype "passive"))
      (node (ref "C336") (pin "2") (pinfunction "2_2") (pintype "passive"))
      (node (ref "C337") (pin "1") (pinfunction "1_1") (pintype "passive"))
      (node (ref "C338") (pin "2") (pinfunction "2_2") (pintype "passive"))
      (node (ref "C339") (pin "1") (pinfunction "1_1") (pintype "passive"))
      (node (ref "C340") (pin "2") (pinfunction "2_2") (pintype "passive"))
      (node (ref "C341") (pin "1") (pinfunction "1_1") (pintype "passive"))
      (node (ref "C342") (pin "2") (pinfunction "2_2") (pintype "passive"))
      (node (ref "C343") (pin "1") (pinfunction "1_1") (pintype "passive"))
      (node (ref "C344") (pin "2") (pinfunction "2_2") (pintype "passive"))
      (node (ref "C345") (pin "1") (pinfunction "1_1") (pintype "passive"))
      (node (ref "C346") (pin "2") (pinfunction "2_2") (pintype "passive"))
      (node (ref "C347") (pin "1") (pinfunction "1_1") (pintype "passive"))
      (node (ref "C348") (pin "2") (pinfunction "2_2") (pintype "passive"))
      (node (ref "C349") (pin "1") (pinfunction "1_1") (pintype "passive"))
      (node (ref "C350") (pin "2") (pinfunction "2_2") (pintype "passive"))
      (node (ref "C351") (pin "1") (pinfunction "1_1") (pintype "passive"))
      (node (ref "C352") (pin "2") (pinfunction "2_2") (pintype "passive"))
      (node (ref "C353") (pin "1") (pinfunction "1_1") (pintype "passive"))
      (node (ref "C354") (pin "2") (pinfunction "2_2") (pintype "passive"))
      (node (ref "C355") (pin "1") (pinfunction "1_1") (pintype "passive"))
      (node (ref "C356") (pin "2") (pinfunction "2_2") (pintype "passive"))
      (node (ref "C357") (pin "1") (pinfunction "1_1") (pintype "passive"))
      (node (ref "C358") (pin "2") (pinfunction "2_2") (pintype "passive"))
      (node (ref "C359") (pin "1") (pinfunction "1_1") (pintype "passive"))
      (node (ref "C360") (pin "2") (pinfunction "2_2") (pintype "passive"))
      (node (ref "C361") (pin "1") (pinfunction "1_1") (pintype "passive"))
      (node (ref "C362") (pin "2") (pinfunction "2_2") (pintype "passive"))
      (node (ref "C363") (pin "1") (pinfunction "1_1") (pintype "passive"))
      (node (ref "C364") (pin "2") (pinfunction "2_2") (pintype "passive"))
      (node (ref "C365") (pin "1") (pinfunction "1_1") (pintype "passive"))
      (node (ref "C366") (pin "2") (pinfunction "2_2") (pintype "passive"))
      (node (ref "C367") (pin "1") (pinfunction "1_1") (pintype "passive"))
      (node (ref "C368") (pin "2") (pinfunction "2_2") (pintype "passive"))
      (node (ref "C369") (pin "2") (pinfunction "2_2") (pintype "passive"))
      (node (ref "C370") (pin "2") (pinfunction "2_2") (pintype "passive"))
      (node (ref "C371") (pin "2") (pinfunction "2_2") (pintype "passive"))
      (node (ref "C372") (pin "2") (pinfunction "2_2") (pintype "passive"))
      (node (ref "C373") (pin "2") (pinfunction "2_2") (pintype "passive"))
      (node (ref "C374") (pin "2") (pinfunction "2_2") (pintype "passive"))
      (node (ref "C375") (pin "2") (pinfunction "2_2") (pintype "passive"))
      (node (ref "C376") (pin "2") (pinfunction "2_2") (pintype "passive"))
      (node (ref "C377") (pin "2") (pinfunction "2_2") (pintype "passive"))
      (node (ref "C378") (pin "2") (pinfunction "2_2") (pintype "passive"))
      (node (ref "C379") (pin "2") (pinfunction "2_2") (pintype "passive"))
      (node (ref "C380") (pin "2") (pinfunction "2_2") (pintype "passive"))
      (node (ref "C381") (pin "1") (pinfunction "1_1") (pintype "passive"))
      (node (ref "C382") (pin "1") (pinfunction "1_1") (pintype "passive"))
      (node (ref "C383") (pin "1") (pinfunction "1_1") (pintype "passive"))
      (node (ref "C384") (pin "2") (pinfunction "2_2") (pintype "passive"))
      (node (ref "C385") (pin "2") (pinfunction "2_2") (pintype "passive"))
      (node (ref "C386") (pin "1") (pinfunction "1_1") (pintype "passive"))
      (node (ref "C387") (pin "1") (pinfunction "1_1") (pintype "passive"))
      (node (ref "C388") (pin "2") (pinfunction "2_2") (pintype "passive"))
      (node (ref "C389") (pin "2") (pinfunction "2_2") (pintype "passive"))
      (node (ref "C390") (pin "1") (pinfunction "1_1") (pintype "passive"))
      (node (ref "C391") (pin "1") (pinfunction "1_1") (pintype "passive"))
      (node (ref "C392") (pin "2") (pinfunction "2_2") (pintype "passive"))
      (node (ref "C393") (pin "2") (pinfunction "2_2") (pintype "passive"))
      (node (ref "C394") (pin "1") (pinfunction "1_1") (pintype "passive"))
      (node (ref "C395") (pin "1") (pinfunction "1_1") (pintype "passive"))
      (node (ref "C396") (pin "2") (pinfunction "2_2") (pintype "passive"))
      (node (ref "C397") (pin "2") (pinfunction "2_2") (pintype "passive"))
      (node (ref "C398") (pin "1") (pinfunction "1_1") (pintype "passive"))
      (node (ref "C399") (pin "2") (pinfunction "2_2") (pintype "passive"))
      (node (ref "C400") (pin "2") (pinfunction "2_2") (pintype "passive"))
      (node (ref "C401") (pin "2") (pinfunction "2_2") (pintype "passive"))
      (node (ref "C402") (pin "2") (pinfunction "2_2") (pintype "passive"))
      (node (ref "C403") (pin "2") (pinfunction "2_2") (pintype "passive"))
      (node (ref "C404") (pin "2") (pinfunction "2_2") (pintype "passive"))
      (node (ref "C405") (pin "2") (pinfunction "2_2") (pintype "passive"))
      (node (ref "C406") (pin "2") (pinfunction "2_2") (pintype "passive"))
      (node (ref "R237") (pin "2") (pinfunction "2_2") (pintype "passive"))
      (node (ref "R238") (pin "2") (pinfunction "2_2") (pintype "passive"))
      (node (ref "R239") (pin "2") (pinfunction "2_2") (pintype "passive"))
      (node (ref "R240") (pin "2") (pinfunction "2_2") (pintype "passive"))
      (node (ref "R245") (pin "2") (pinfunction "2_2") (pintype "passive"))
      (node (ref "R246") (pin "2") (pinfunction "2_2") (pintype "passive"))
      (node (ref "R247") (pin "2") (pinfunction "2_2") (pintype "passive"))
      (node (ref "R248") (pin "2") (pinfunction "2_2") (pintype "passive"))
      (node (ref "R253") (pin "2") (pinfunction "2_2") (pintype "passive"))
      (node (ref "U28") (pin "12") (pinfunction "EP_12") (pintype "power_in"))
      (node (ref "U28") (pin "3") (pinfunction "SYNC_3") (pintype "input"))
      (node (ref "U28") (pin "5") (pinfunction "AGND_5") (pintype "power_in"))
      (node (ref "U28") (pin "6") (pinfunction "AGND_6") (pintype "power_in"))
      (node (ref "U29") (pin "12") (pinfunction "EP_12") (pintype "power_in"))
      (node (ref "U29") (pin "3") (pinfunction "SYNC_3") (pintype "input"))
      (node (ref "U29") (pin "5") (pinfunction "AGND_5") (pintype "power_in"))
      (node (ref "U29") (pin "6") (pinfunction "AGND_6") (pintype "power_in"))
      (node (ref "U30") (pin "12") (pinfunction "EP_12") (pintype "power_in"))
      (node (ref "U30") (pin "3") (pinfunction "SYNC_3") (pintype "input"))
      (node (ref "U30") (pin "5") (pinfunction "AGND_5") (pintype "power_in"))
      (node (ref "U30") (pin "6") (pinfunction "AGND_6") (pintype "power_in"))
      (node (ref "U31") (pin "12") (pinfunction "EP_12") (pintype "power_in"))
      (node (ref "U31") (pin "3") (pinfunction "SYNC_3") (pintype "input"))
      (node (ref "U31") (pin "5") (pinfunction "AGND_5") (pintype "power_in"))
      (node (ref "U31") (pin "6") (pinfunction "AGND_6") (pintype "power_in"))
      (node (ref "U32") (pin "12") (pinfunction "EP_12") (pintype "power_in"))
      (node (ref "U32") (pin "3") (pinfunction "SYNC_3") (pintype "input"))
      (node (ref "U32") (pin "5") (pinfunction "AGND_5") (pintype "power_in"))
      (node (ref "U32") (pin "6") (pinfunction "AGND_6") (pintype "power_in"))
      (node (ref "U33") (pin "12") (pinfunction "EP_12") (pintype "power_in"))
      (node (ref "U33") (pin "3") (pinfunction "SYNC_3") (pintype "input"))
      (node (ref "U33") (pin "5") (pinfunction "AGND_5") (pintype "power_in"))
      (node (ref "U33") (pin "6") (pinfunction "AGND_6") (pintype "power_in"))
      (node (ref "U34") (pin "12") (pinfunction "EP_12") (pintype "power_in"))
      (node (ref "U34") (pin "3") (pinfunction "SYNC_3") (pintype "input"))
      (node (ref "U34") (pin "5") (pinfunction "AGND_5") (pintype "power_in"))
      (node (ref "U34") (pin "6") (pinfunction "AGND_6") (pintype "power_in"))
      (node (ref "U35") (pin "12") (pinfunction "EP_12") (pintype "power_in"))
      (node (ref "U35") (pin "3") (pinfunction "SYNC_3") (pintype "input"))
      (node (ref "U35") (pin "5") (pinfunction "AGND_5") (pintype "power_in"))
      (node (ref "U35") (pin "6") (pinfunction "AGND_6") (pintype "power_in"))
      (node (ref "U36") (pin "4") (pinfunction "GND_4") (pintype "passive"))
      (node (ref "U36") (pin "5") (pinfunction "A2_5") (pintype "passive"))
      (node (ref "U36") (pin "6") (pinfunction "A1_6") (pintype "passive"))
      (node (ref "U36") (pin "7") (pinfunction "A0_7") (pintype "passive"))
      (node (ref "U36") (pin "9") (pinfunction "GND_9") (pintype "passive"))
      (node (ref "U37") (pin "4") (pinfunction "GND_4") (pintype "passive"))
      (node (ref "U37") (pin "5") (pinfunction "A2_5") (pintype "passive"))
      (node (ref "U37") (pin "6") (pinfunction "A1_6") (pintype "passive"))
      (node (ref "U37") (pin "9") (pinfunction "GND_9") (pintype "passive"))
      (node (ref "U38") (pin "12") (pinfunction "EP_12") (pintype "power_in"))
      (node (ref "U38") (pin "5") (pinfunction "AGND_5") (pintype "power_in"))
      (node (ref "U38") (pin "6") (pinfunction "AGND_6") (pintype "power_in"))
      (node (ref "U39") (pin "12") (pinfunction "EP_12") (pintype "power_in"))
      (node (ref "U39") (pin "5") (pinfunction "AGND_5") (pintype "power_in"))
      (node (ref "U39") (pin "6") (pinfunction "AGND_6") (pintype "power_in"))
      (node (ref "U40") (pin "3") (pinfunction "GND_3") (pintype "passive"))
      (node (ref "U41") (pin "3") (pinfunction "GND_3") (pintype "passive"))
    )
    (net (code "19") (name "MGTAVCC") (class "Default")
      (node (ref "C340") (pin "1") (pinfunction "1_1") (pintype "passive"))
      (node (ref "C348") (pin "1") (pinfunction "1_1") (pintype "passive"))
      (node (ref "C356") (pin "1") (pinfunction "1_1") (pintype "passive"))
      (node (ref "C364") (pin "1") (pinfunction "1_1") (pintype "passive"))
      (node (ref "C372") (pin "1") (pinfunction "1_1") (pintype "passive"))
      (node (ref "C412") (pin "2") (pinfunction "2_2") (pintype "passive"))
      (node (ref "R242") (pin "2") (pinfunction "2_2") (pintype "passive"))
      (node (ref "U33") (pin "10") (pinfunction "VOUT_10") (pintype "power_in"))
      (node (ref "U33") (pin "11") (pinfunction "VOUT_11") (pintype "power_in"))
    )
    (net (code "20") (name "MGTAVTT") (class "Default")
      (node (ref "C338") (pin "1") (pinfunction "1_1") (pintype "passive"))
      (node (ref "C346") (pin "1") (pinfunction "1_1") (pintype "passive"))
      (node (ref "C354") (pin "1") (pinfunction "1_1") (pintype "passive"))
      (node (ref "C362") (pin "1") (pinfunction "1_1") (pintype "passive"))
      (node (ref "C370") (pin "1") (pinfunction "1_1") (pintype "passive"))
      (node (ref "C411") (pin "2") (pinfunction "2_2") (pintype "passive"))
      (node (ref "R241") (pin "2") (pinfunction "2_2") (pintype "passive"))
      (node (ref "U32") (pin "10") (pinfunction "VOUT_10") (pintype "power_in"))
      (node (ref "U32") (pin "11") (pinfunction "VOUT_11") (pintype "power_in"))
    )
    (net (code "21") (name "Net-(U28-FB)") (class "Default")
      (node (ref "C407") (pin "1") (pinfunction "1_1") (pintype "passive"))
      (node (ref "R233") (pin "1") (pinfunction "1_1") (pintype "passive"))
      (node (ref "R237") (pin "1") (pinfunction "1_1") (pintype "passive"))
      (node (ref "U28") (pin "7") (pinfunction "FB_7") (pintype "passive"))
    )
    (net (code "22") (name "Net-(U28-SS)") (class "Default")
      (node (ref "C333") (pin "1") (pinfunction "1_1") (pintype "passive"))
      (node (ref "U28") (pin "8") (pinfunction "SS_8") (pintype "input"))
    )
    (net (code "23") (name "Net-(U29-FB)") (class "Default")
      (node (ref "C408") (pin "1") (pinfunction "1_1") (pintype "passive"))
      (node (ref "R234") (pin "1") (pinfunction "1_1") (pintype "passive"))
      (node (ref "R238") (pin "1") (pinfunction "1_1") (pintype "passive"))
      (node (ref "U29") (pin "7") (pinfunction "FB_7") (pintype "passive"))
    )
    (net (code "24") (name "Net-(U29-SS)") (class "Default")
      (node (ref "C334") (pin "1") (pinfunction "1_1") (pintype "passive"))
      (node (ref "U29") (pin "8") (pinfunction "SS_8") (pintype "input"))
    )
    (net (code "25") (name "Net-(U30-FB)") (class "Default")
      (node (ref "C409") (pin "1") (pinfunction "1_1") (pintype "passive"))
      (node (ref "R235") (pin "1") (pinfunction "1_1") (pintype "passive"))
      (node (ref "R239") (pin "1") (pinfunction "1_1") (pintype "passive"))
      (node (ref "U30") (pin "7") (pinfunction "FB_7") (pintype "passive"))
    )
    (net (code "26") (name "Net-(U30-SS)") (class "Default")
      (node (ref "C335") (pin "1") (pinfunction "1_1") (pintype "passive"))
      (node (ref "U30") (pin "8") (pinfunction "SS_8") (pintype "input"))
    )
    (net (code "27") (name "Net-(U31-FB)") (class "Default")
      (node (ref "C410") (pin "1") (pinfunction "1_1") (pintype "passive"))
      (node (ref "R236") (pin "1") (pinfunction "1_1") (pintype "passive"))
      (node (ref "R240") (pin "1") (pinfunction "1_1") (pintype "passive"))
      (node (ref "U31") (pin "7") (pinfunction "FB_7") (pintype "passive"))
    )
    (net (code "28") (name "Net-(U31-SS)") (class "Default")
      (node (ref "C336") (pin "1") (pinfunction "1_1") (pintype "passive"))
      (node (ref "U31") (pin "8") (pinfunction "SS_8") (pintype "input"))
    )
    (net (code "29") (name "Net-(U32-FB)") (class "Default")
      (node (ref "C411") (pin "1") (pinfunction "1_1") (pintype "passive"))
      (node (ref "R241") (pin "1") (pinfunction "1_1") (pintype "passive"))
      (node (ref "R245") (pin "1") (pinfunction "1_1") (pintype "passive"))
      (node (ref "U32") (pin "7") (pinfunction "FB_7") (pintype "passive"))
    )
    (net (code "30") (name "Net-(U32-SS)") (class "Default")
      (node (ref "C377") (pin "1") (pinfunction "1_1") (pintype "passive"))
      (node (ref "U32") (pin "8") (pinfunction "SS_8") (pintype "input"))
    )
    (net (code "31") (name "Net-(U33-FB)") (class "Default")
      (node (ref "C412") (pin "1") (pinfunction "1_1") (pintype "passive"))
      (node (ref "R242") (pin "1") (pinfunction "1_1") (pintype "passive"))
      (node (ref "R246") (pin "1") (pinfunction "1_1") (pintype "passive"))
      (node (ref "U33") (pin "7") (pinfunction "FB_7") (pintype "passive"))
    )
    (net (code "32") (name "Net-(U33-SS)") (class "Default")
      (node (ref "C378") (pin "1") (pinfunction "1_1") (pintype "passive"))
      (node (ref "U33") (pin "8") (pinfunction "SS_8") (pintype "input"))
    )
    (net (code "33") (name "Net-(U34-FB)") (class "Default")
      (node (ref "C413") (pin "1") (pinfunction "1_1") (pintype "passive"))
      (node (ref "R243") (pin "1") (pinfunction "1_1") (pintype "passive"))
      (node (ref "R247") (pin "1") (pinfunction "1_1") (pintype "passive"))
      (node (ref "U34") (pin "7") (pinfunction "FB_7") (pintype "passive"))
    )
    (net (code "34") (name "Net-(U34-SS)") (class "Default")
      (node (ref "C379") (pin "1") (pinfunction "1_1") (pintype "passive"))
      (node (ref "U34") (pin "8") (pinfunction "SS_8") (pintype "input"))
    )
    (net (code "35") (name "Net-(U35-FB)") (class "Default")
      (node (ref "C414") (pin "1") (pinfunction "1_1") (pintype "passive"))
      (node (ref "R244") (pin "1") (pinfunction "1_1") (pintype "passive"))
      (node (ref "R248") (pin "1") (pinfunction "1_1") (pintype "passive"))
      (node (ref "U35") (pin "7") (pinfunction "FB_7") (pintype "passive"))
    )
    (net (code "36") (name "Net-(U35-SS)") (class "Default")
      (node (ref "C380") (pin "1") (pinfunction "1_1") (pintype "passive"))
      (node (ref "U35") (pin "8") (pinfunction "SS_8") (pintype "input"))
    )
    (net (code "37") (name "Net-(U38-FB)") (class "Default")
      (node (ref "C415") (pin "1") (pinfunction "1_1") (pintype "passive"))
      (node (ref "R252") (pin "1") (pinfunction "1_1") (pintype "passive"))
      (node (ref "R253") (pin "1") (pinfunction "1_1") (pintype "passive"))
      (node (ref "U38") (pin "7") (pinfunction "FB_7") (pintype "passive"))
    )
    (net (code "38") (name "Net-(U38-SH)") (class "Default")
      (node (ref "U38") (pin "9") (pinfunction "SH_9") (pintype "passive"))
      (node (ref "U39") (pin "9") (pinfunction "SH_9") (pintype "passive"))
    )
    (net (code "39") (name "Net-(U38-SS)") (class "Default")
      (node (ref "C406") (pin "1") (pinfunction "1_1") (pintype "passive"))
      (node (ref "U38") (pin "8") (pinfunction "SS_8") (pintype "input"))
    )
    (net (code "40") (name "Net-(U41-A)") (class "Default")
      (node (ref "C405") (pin "1") (pinfunction "1_1") (pintype "passive"))
      (node (ref "R251") (pin "2") (pinfunction "2_2") (pintype "passive"))
      (node (ref "U41") (pin "2") (pinfunction "A_2") (pintype "passive"))
    )
    (net (code "41") (name "VCC1V0_FPGA") (class "Default")
      (node (ref "C384") (pin "1") (pinfunction "1_1") (pintype "passive"))
      (node (ref "C385") (pin "1") (pinfunction "1_1") (pintype "passive"))
      (node (ref "C388") (pin "1") (pinfunction "1_1") (pintype "passive"))
      (node (ref "C389") (pin "1") (pinfunction "1_1") (pintype "passive"))
      (node (ref "C392") (pin "1") (pinfunction "1_1") (pintype "passive"))
      (node (ref "C393") (pin "1") (pinfunction "1_1") (pintype "passive"))
      (node (ref "C396") (pin "1") (pinfunction "1_1") (pintype "passive"))
      (node (ref "C397") (pin "1") (pinfunction "1_1") (pintype "passive"))
      (node (ref "C402") (pin "1") (pinfunction "1_1") (pintype "passive"))
      (node (ref "C403") (pin "1") (pinfunction "1_1") (pintype "passive"))
      (node (ref "C415") (pin "2") (pinfunction "2_2") (pintype "passive"))
      (node (ref "R252") (pin "2") (pinfunction "2_2") (pintype "passive"))
      (node (ref "U38") (pin "10") (pinfunction "VOUT_10") (pintype "power_in"))
      (node (ref "U38") (pin "11") (pinfunction "VOUT_11") (pintype "power_in"))
      (node (ref "U39") (pin "10") (pinfunction "VOUT_10") (pintype "power_in"))
      (node (ref "U39") (pin "11") (pinfunction "VOUT_11") (pintype "power_in"))
    )
    (net (code "42") (name "VCC1V5") (class "Default")
      (node (ref "C300") (pin "1") (pinfunction "1_1") (pintype "passive"))
      (node (ref "C308") (pin "1") (pinfunction "1_1") (pintype "passive"))
      (node (ref "C316") (pin "1") (pinfunction "1_1") (pintype "passive"))
      (node (ref "C324") (pin "1") (pinfunction "1_1") (pintype "passive"))
      (node (ref "C332") (pin "1") (pinfunction "1_1") (pintype "passive"))
      (node (ref "C410") (pin "2") (pinfunction "2_2") (pintype "passive"))
      (node (ref "R236") (pin "2") (pinfunction "2_2") (pintype "passive"))
      (node (ref "U31") (pin "10") (pinfunction "VOUT_10") (pintype "power_in"))
      (node (ref "U31") (pin "11") (pinfunction "VOUT_11") (pintype "power_in"))
    )
    (net (code "43") (name "VCC1V8") (class "Default")
      (node (ref "C296") (pin "1") (pinfunction "1_1") (pintype "passive"))
      (node (ref "C304") (pin "1") (pinfunction "1_1") (pintype "passive"))
      (node (ref "C312") (pin "1") (pinfunction "1_1") (pintype "passive"))
      (node (ref "C320") (pin "1") (pinfunction "1_1") (pintype "passive"))
      (node (ref "C328") (pin "1") (pinfunction "1_1") (pintype "passive"))
      (node (ref "C408") (pin "2") (pinfunction "2_2") (pintype "passive"))
      (node (ref "R234") (pin "2") (pinfunction "2_2") (pintype "passive"))
      (node (ref "U29") (pin "10") (pinfunction "VOUT_10") (pintype "power_in"))
      (node (ref "U29") (pin "11") (pinfunction "VOUT_11") (pintype "power_in"))
    )
    (net (code "44") (name "VCC1V8_AUX") (class "Default")
      (node (ref "C298") (pin "1") (pinfunction "1_1") (pintype "passive"))
      (node (ref "C306") (pin "1") (pinfunction "1_1") (pintype "passive"))
      (node (ref "C314") (pin "1") (pinfunction "1_1") (pintype "passive"))
      (node (ref "C322") (pin "1") (pinfunction "1_1") (pintype "passive"))
      (node (ref "C330") (pin "1") (pinfunction "1_1") (pintype "passive"))
      (node (ref "C409") (pin "2") (pinfunction "2_2") (pintype "passive"))
      (node (ref "R235") (pin "2") (pinfunction "2_2") (pintype "passive"))
      (node (ref "U30") (pin "10") (pinfunction "VOUT_10") (pintype "power_in"))
      (node (ref "U30") (pin "11") (pinfunction "VOUT_11") (pintype "power_in"))
    )
    (net (code "45") (name "VCC2V5") (class "Default")
      (node (ref "C342") (pin "1") (pinfunction "1_1") (pintype "passive"))
      (node (ref "C350") (pin "1") (pinfunction "1_1") (pintype "passive"))
      (node (ref "C358") (pin "1") (pinfunction "1_1") (pintype "passive"))
      (node (ref "C366") (pin "1") (pinfunction "1_1") (pintype "passive"))
      (node (ref "C374") (pin "1") (pinfunction "1_1") (pintype "passive"))
      (node (ref "C413") (pin "2") (pinfunction "2_2") (pintype "passive"))
      (node (ref "R243") (pin "2") (pinfunction "2_2") (pintype "passive"))
      (node (ref "U34") (pin "10") (pinfunction "VOUT_10") (pintype "power_in"))
      (node (ref "U34") (pin "11") (pinfunction "VOUT_11") (pintype "power_in"))
    )
    (net (code "46") (name "VCC3V3") (class "Default")
      (node (ref "C344") (pin "1") (pinfunction "1_1") (pintype "passive"))
      (node (ref "C352") (pin "1") (pinfunction "1_1") (pintype "passive"))
      (node (ref "C360") (pin "1") (pinfunction "1_1") (pintype "passive"))
      (node (ref "C368") (pin "1") (pinfunction "1_1") (pintype "passive"))
      (node (ref "C376") (pin "1") (pinfunction "1_1") (pintype "passive"))
      (node (ref "C381") (pin "2") (pinfunction "2_2") (pintype "passive"))
      (node (ref "C382") (pin "2") (pinfunction "2_2") (pintype "passive"))
      (node (ref "C414") (pin "2") (pinfunction "2_2") (pintype "passive"))
      (node (ref "R244") (pin "2") (pinfunction "2_2") (pintype "passive"))
      (node (ref "U35") (pin "10") (pinfunction "VOUT_10") (pintype "power_in"))
      (node (ref "U35") (pin "11") (pinfunction "VOUT_11") (pintype "power_in"))
      (node (ref "U36") (pin "8") (pinfunction "VCC_8") (pintype "passive"))
      (node (ref "U37") (pin "7") (pinfunction "A0_7") (pintype "passive"))
      (node (ref "U37") (pin "8") (pinfunction "VCC_8") (pintype "passive"))
    )
    (net (code "47") (name "VCC5V") (class "Default")
      (node (ref "C294") (pin "1") (pinfunction "1_1") (pintype "passive"))
      (node (ref "C302") (pin "1") (pinfunction "1_1") (pintype "passive"))
      (node (ref "C310") (pin "1") (pinfunction "1_1") (pintype "passive"))
      (node (ref "C318") (pin "1") (pinfunction "1_1") (pintype "passive"))
      (node (ref "C326") (pin "1") (pinfunction "1_1") (pintype "passive"))
      (node (ref "C407") (pin "2") (pinfunction "2_2") (pintype "passive"))
      (node (ref "R233") (pin "2") (pinfunction "2_2") (pintype "passive"))
      (node (ref "U28") (pin "10") (pinfunction "VOUT_10") (pintype "power_in"))
      (node (ref "U28") (pin "11") (pinfunction "VOUT_11") (pintype "power_in"))
    )
    (net (code "48") (name "VCC5V_SB") (class "Default")
      (node (ref "C399") (pin "1") (pinfunction "1_1") (pintype "passive"))
      (node (ref "C400") (pin "1") (pinfunction "1_1") (pintype "passive"))
      (node (ref "U40") (pin "5") (pinfunction "VCC_5") (pintype "passive"))
      (node (ref "U41") (pin "5") (pinfunction "VCC_5") (pintype "passive"))
    )
    (net (code "49") (name "VCC12V") (class "Default")
      (node (ref "C293") (pin "2") (pinfunction "2_2") (pintype "passive"))
      (node (ref "C295") (pin "2") (pinfunction "2_2") (pintype "passive"))
      (node (ref "C297") (pin "2") (pinfunction "2_2") (pintype "passive"))
      (node (ref "C299") (pin "2") (pinfunction "2_2") (pintype "passive"))
      (node (ref "C301") (pin "2") (pinfunction "2_2") (pintype "passive"))
      (node (ref "C303") (pin "2") (pinfunction "2_2") (pintype "passive"))
      (node (ref "C305") (pin "2") (pinfunction "2_2") (pintype "passive"))
      (node (ref "C307") (pin "2") (pinfunction "2_2") (pintype "passive"))
      (node (ref "C309") (pin "2") (pinfunction "2_2") (pintype "passive"))
      (node (ref "C311") (pin "2") (pinfunction "2_2") (pintype "passive"))
      (node (ref "C313") (pin "2") (pinfunction "2_2") (pintype "passive"))
      (node (ref "C315") (pin "2") (pinfunction "2_2") (pintype "passive"))
      (node (ref "C317") (pin "2") (pinfunction "2_2") (pintype "passive"))
      (node (ref "C319") (pin "2") (pinfunction "2_2") (pintype "passive"))
      (node (ref "C321") (pin "2") (pinfunction "2_2") (pintype "passive"))
      (node (ref "C323") (pin "2") (pinfunction "2_2") (pintype "passive"))
      (node (ref "C325") (pin "1") (pinfunction "1_1") (pintype "passive"))
      (node (ref "C327") (pin "1") (pinfunction "1_1") (pintype "passive"))
      (node (ref "C329") (pin "1") (pinfunction "1_1") (pintype "passive"))
      (node (ref "C331") (pin "1") (pinfunction "1_1") (pintype "passive"))
      (node (ref "C337") (pin "2") (pinfunction "2_2") (pintype "passive"))
      (node (ref "C339") (pin "2") (pinfunction "2_2") (pintype "passive"))
      (node (ref "C341") (pin "2") (pinfunction "2_2") (pintype "passive"))
      (node (ref "C343") (pin "2") (pinfunction "2_2") (pintype "passive"))
      (node (ref "C345") (pin "2") (pinfunction "2_2") (pintype "passive"))
      (node (ref "C347") (pin "2") (pinfunction "2_2") (pintype "passive"))
      (node (ref "C349") (pin "2") (pinfunction "2_2") (pintype "passive"))
      (node (ref "C351") (pin "2") (pinfunction "2_2") (pintype "passive"))
      (node (ref "C353") (pin "2") (pinfunction "2_2") (pintype "passive"))
      (node (ref "C355") (pin "2") (pinfunction "2_2") (pintype "passive"))
      (node (ref "C357") (pin "2") (pinfunction "2_2") (pintype "passive"))
      (node (ref "C359") (pin "2") (pinfunction "2_2") (pintype "passive"))
      (node (ref "C361") (pin "2") (pinfunction "2_2") (pintype "passive"))
      (node (ref "C363") (pin "2") (pinfunction "2_2") (pintype "passive"))
      (node (ref "C365") (pin "2") (pinfunction "2_2") (pintype "passive"))
      (node (ref "C367") (pin "2") (pinfunction "2_2") (pintype "passive"))
      (node (ref "C369") (pin "1") (pinfunction "1_1") (pintype "passive"))
      (node (ref "C371") (pin "1") (pinfunction "1_1") (pintype "passive"))
      (node (ref "C373") (pin "1") (pinfunction "1_1") (pintype "passive"))
      (node (ref "C375") (pin "1") (pinfunction "1_1") (pintype "passive"))
      (node (ref "C383") (pin "2") (pinfunction "2_2") (pintype "passive"))
      (node (ref "C386") (pin "2") (pinfunction "2_2") (pintype "passive"))
      (node (ref "C387") (pin "2") (pinfunction "2_2") (pintype "passive"))
      (node (ref "C390") (pin "2") (pinfunction "2_2") (pintype "passive"))
      (node (ref "C391") (pin "2") (pinfunction "2_2") (pintype "passive"))
      (node (ref "C394") (pin "2") (pinfunction "2_2") (pintype "passive"))
      (node (ref "C395") (pin "2") (pinfunction "2_2") (pintype "passive"))
      (node (ref "C398") (pin "2") (pinfunction "2_2") (pintype "passive"))
      (node (ref "C401") (pin "1") (pinfunction "1_1") (pintype "passive"))
      (node (ref "C404") (pin "1") (pinfunction "1_1") (pintype "passive"))
      (node (ref "U28") (pin "1") (pinfunction "VIN_1") (pintype "power_in"))
      (node (ref "U28") (pin "2") (pinfunction "VIN_2") (pintype "power_in"))
      (node (ref "U29") (pin "1") (pinfunction "VIN_1") (pintype "power_in"))
      (node (ref "U29") (pin "2") (pinfunction "VIN_2") (pintype "power_in"))
      (node (ref "U30") (pin "1") (pinfunction "VIN_1") (pintype "power_in"))
      (node (ref "U30") (pin "2") (pinfunction "VIN_2") (pintype "power_in"))
      (node (ref "U31") (pin "1") (pinfunction "VIN_1") (pintype "power_in"))
      (node (ref "U31") (pin "2") (pinfunction "VIN_2") (pintype "power_in"))
      (node (ref "U32") (pin "1") (pinfunction "VIN_1") (pintype "power_in"))
      (node (ref "U32") (pin "2") (pinfunction "VIN_2") (pintype "power_in"))
      (node (ref "U33") (pin "1") (pinfunction "VIN_1") (pintype "power_in"))
      (node (ref "U33") (pin "2") (pinfunction "VIN_2") (pintype "power_in"))
      (node (ref "U34") (pin "1") (pinfunction "VIN_1") (pintype "power_in"))
      (node (ref "U34") (pin "2") (pinfunction "VIN_2") (pintype "power_in"))
      (node (ref "U35") (pin "1") (pinfunction "VIN_1") (pintype "power_in"))
      (node (ref "U35") (pin "2") (pinfunction "VIN_2") (pintype "power_in"))
      (node (ref "U38") (pin "1") (pinfunction "VIN_1") (pintype "power_in"))
      (node (ref "U38") (pin "2") (pinfunction "VIN_2") (pintype "power_in"))
      (node (ref "U39") (pin "1") (pinfunction "VIN_1") (pintype "power_in"))
      (node (ref "U39") (pin "2") (pinfunction "VIN_2") (pintype "power_in"))
    )
    (net (code "50") (name "unconnected-(U28-SH-Pad9)") (class "Default")
      (node (ref "U28") (pin "9") (pinfunction "SH_9") (pintype "passive"))
    )
    (net (code "51") (name "unconnected-(U29-SH-Pad9)") (class "Default")
      (node (ref "U29") (pin "9") (pinfunction "SH_9") (pintype "passive"))
    )
    (net (code "52") (name "unconnected-(U30-SH-Pad9)") (class "Default")
      (node (ref "U30") (pin "9") (pinfunction "SH_9") (pintype "passive"))
    )
    (net (code "53") (name "unconnected-(U31-SH-Pad9)") (class "Default")
      (node (ref "U31") (pin "9") (pinfunction "SH_9") (pintype "passive"))
    )
    (net (code "54") (name "unconnected-(U32-SH-Pad9)") (class "Default")
      (node (ref "U32") (pin "9") (pinfunction "SH_9") (pintype "passive"))
    )
    (net (code "55") (name "unconnected-(U33-SH-Pad9)") (class "Default")
      (node (ref "U33") (pin "9") (pinfunction "SH_9") (pintype "passive"))
    )
    (net (code "56") (name "unconnected-(U34-SH-Pad9)") (class "Default")
      (node (ref "U34") (pin "9") (pinfunction "SH_9") (pintype "passive"))
    )
    (net (code "57") (name "unconnected-(U35-SH-Pad9)") (class "Default")
      (node (ref "U35") (pin "9") (pinfunction "SH_9") (pintype "passive"))
    )
    (net (code "58") (name "unconnected-(U36-OS-Pad3)") (class "Default")
      (node (ref "U36") (pin "3") (pinfunction "OS_3") (pintype "passive"))
    )
    (net (code "59") (name "unconnected-(U37-OS-Pad3)") (class "Default")
      (node (ref "U37") (pin "3") (pinfunction "OS_3") (pintype "passive"))
    )
    (net (code "60") (name "unconnected-(U39-FB-Pad7)") (class "Default")
      (node (ref "U39") (pin "7") (pinfunction "FB_7") (pintype "passive+no_connect"))
    )
    (net (code "61") (name "unconnected-(U39-SS-Pad8)") (class "Default")
      (node (ref "U39") (pin "8") (pinfunction "SS_8") (pintype "input+no_connect"))
    )
  )
)
